# main_schematic.net
KiCad netlist of a schematic drawn in Altium Designer
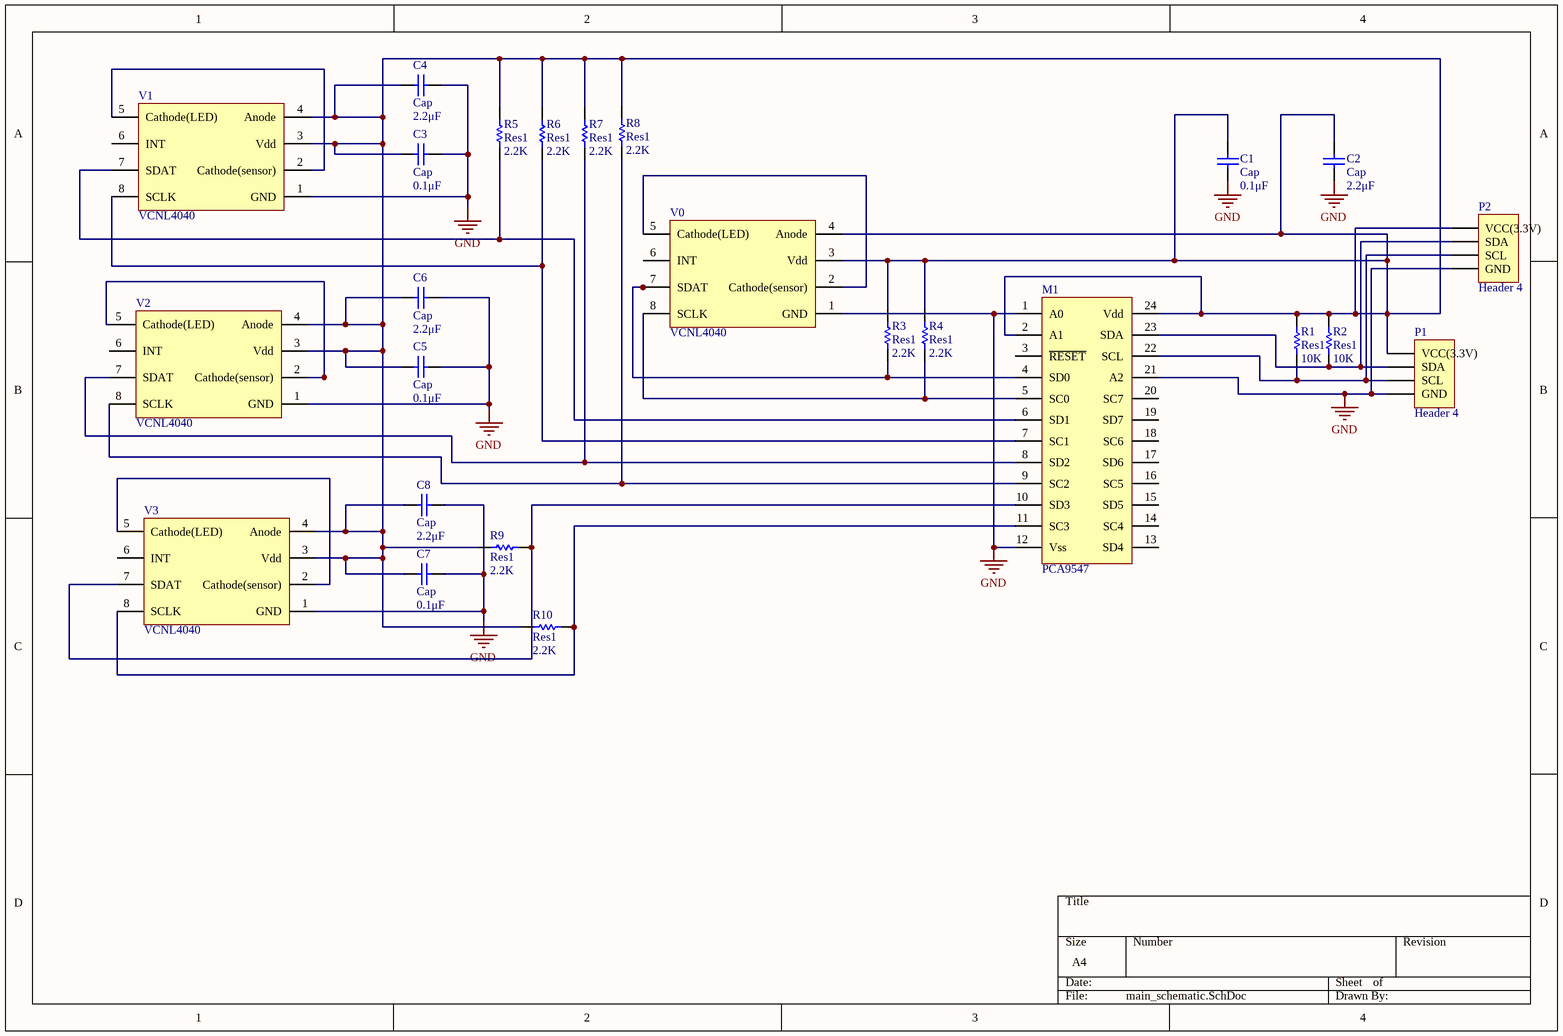
[diagram p0: main_schematic.SchDoc]

(export (version "E")
  (design (tool "Eeschema 10.0.6"))
  (components
    (comp (ref "C1")
      (value "Cap")
      (footprint "1608[0603]")
      (description "Capacitor")
      (fields (field (name "ALTIUM_VALUE") "0.1μF") (field (name "PUBLISHER") "Altium Limited"))
      (libsource (lib "Miscellaneous Devices") (part "Cap"))
    )
    (comp (ref "C2")
      (value "Cap")
      (footprint "1608[0603]")
      (description "Capacitor")
      (fields (field (name "ALTIUM_VALUE") "2.2μF") (field (name "PUBLISHER") "Altium Limited"))
      (libsource (lib "Miscellaneous Devices") (part "Cap"))
    )
    (comp (ref "C3")
      (value "Cap")
      (footprint "1608[0603]")
      (description "Capacitor")
      (fields (field (name "ALTIUM_VALUE") "0.1μF") (field (name "PUBLISHER") "Altium Limited"))
      (libsource (lib "Miscellaneous Devices") (part "Cap"))
    )
    (comp (ref "C4")
      (value "Cap")
      (footprint "1608[0603]")
      (description "Capacitor")
      (fields (field (name "ALTIUM_VALUE") "2.2μF") (field (name "PUBLISHER") "Altium Limited"))
      (libsource (lib "Miscellaneous Devices") (part "Cap"))
    )
    (comp (ref "C5")
      (value "Cap")
      (footprint "1608[0603]")
      (description "Capacitor")
      (fields (field (name "ALTIUM_VALUE") "0.1μF") (field (name "PUBLISHER") "Altium Limited"))
      (libsource (lib "Miscellaneous Devices") (part "Cap"))
    )
    (comp (ref "C6")
      (value "Cap")
      (footprint "1608[0603]")
      (description "Capacitor")
      (fields (field (name "ALTIUM_VALUE") "2.2μF") (field (name "PUBLISHER") "Altium Limited"))
      (libsource (lib "Miscellaneous Devices") (part "Cap"))
    )
    (comp (ref "C7")
      (value "Cap")
      (footprint "1608[0603]")
      (description "Capacitor")
      (fields (field (name "ALTIUM_VALUE") "0.1μF") (field (name "PUBLISHER") "Altium Limited"))
      (libsource (lib "Miscellaneous Devices") (part "Cap"))
    )
    (comp (ref "C8")
      (value "Cap")
      (footprint "1608[0603]")
      (description "Capacitor")
      (fields (field (name "ALTIUM_VALUE") "2.2μF") (field (name "PUBLISHER") "Altium Limited"))
      (libsource (lib "Miscellaneous Devices") (part "Cap"))
    )
    (comp (ref "M1") (value "PCA9547") (footprint "TSSOP24") (libsource (lib "PCA9547") (part "PCA9547")))
    (comp (ref "P1")
      (value "Header 4")
      (footprint "HDR1X4")
      (description "Header, 4-Pin")
      (fields (field (name "PUBLISHER") "Altium Limited"))
      (libsource (lib "Miscellaneous Connectors") (part "Header 4"))
    )
    (comp (ref "P2")
      (value "Header 4")
      (footprint "HDR1X4")
      (description "Header, 4-Pin")
      (fields (field (name "PUBLISHER") "Altium Limited"))
      (libsource (lib "Miscellaneous Connectors") (part "Header 4"))
    )
    (comp (ref "R1")
      (value "Res1")
      (footprint "1608[0603]")
      (description "Resistor")
      (fields (field (name "ALTIUM_VALUE") "10K") (field (name "PUBLISHER") "Altium Limited"))
      (libsource (lib "Miscellaneous Devices") (part "Res1"))
    )
    (comp (ref "R2")
      (value "Res1")
      (footprint "1608[0603]")
      (description "Resistor")
      (fields (field (name "ALTIUM_VALUE") "10K") (field (name "PUBLISHER") "Altium Limited"))
      (libsource (lib "Miscellaneous Devices") (part "Res1"))
    )
    (comp (ref "R3")
      (value "Res1")
      (footprint "1608[0603]")
      (description "Resistor")
      (fields (field (name "ALTIUM_VALUE") "2.2K") (field (name "PUBLISHER") "Altium Limited"))
      (libsource (lib "Miscellaneous Devices") (part "Res1"))
    )
    (comp (ref "R4")
      (value "Res1")
      (footprint "1608[0603]")
      (description "Resistor")
      (fields (field (name "ALTIUM_VALUE") "2.2K") (field (name "PUBLISHER") "Altium Limited"))
      (libsource (lib "Miscellaneous Devices") (part "Res1"))
    )
    (comp (ref "R5")
      (value "Res1")
      (footprint "1608[0603]")
      (description "Resistor")
      (fields (field (name "ALTIUM_VALUE") "2.2K") (field (name "PUBLISHER") "Altium Limited"))
      (libsource (lib "Miscellaneous Devices") (part "Res1"))
    )
    (comp (ref "R6")
      (value "Res1")
      (footprint "1608[0603]")
      (description "Resistor")
      (fields (field (name "ALTIUM_VALUE") "2.2K") (field (name "PUBLISHER") "Altium Limited"))
      (libsource (lib "Miscellaneous Devices") (part "Res1"))
    )
    (comp (ref "R7")
      (value "Res1")
      (footprint "1608[0603]")
      (description "Resistor")
      (fields (field (name "ALTIUM_VALUE") "2.2K") (field (name "PUBLISHER") "Altium Limited"))
      (libsource (lib "Miscellaneous Devices") (part "Res1"))
    )
    (comp (ref "R8")
      (value "Res1")
      (footprint "1608[0603]")
      (description "Resistor")
      (fields (field (name "ALTIUM_VALUE") "2.2K") (field (name "PUBLISHER") "Altium Limited"))
      (libsource (lib "Miscellaneous Devices") (part "Res1"))
    )
    (comp (ref "R9")
      (value "Res1")
      (footprint "1608[0603]")
      (description "Resistor")
      (fields (field (name "ALTIUM_VALUE") "2.2K") (field (name "PUBLISHER") "Altium Limited"))
      (libsource (lib "Miscellaneous Devices") (part "Res1"))
    )
    (comp (ref "R10")
      (value "Res1")
      (footprint "1608[0603]")
      (description "Resistor")
      (fields (field (name "ALTIUM_VALUE") "2.2K") (field (name "PUBLISHER") "Altium Limited"))
      (libsource (lib "Miscellaneous Devices") (part "Res1"))
    )
    (comp (ref "V0") (value "VCNL4040") (footprint "SOP8") (libsource (lib "VCNL4040") (part "Component_1")))
    (comp (ref "V1") (value "VCNL4040") (footprint "SOP8") (libsource (lib "VCNL4040") (part "Component_1")))
    (comp (ref "V2") (value "VCNL4040") (footprint "SOP8") (libsource (lib "VCNL4040") (part "Component_1")))
    (comp (ref "V3") (value "VCNL4040") (footprint "SOP8") (libsource (lib "VCNL4040") (part "Component_1")))
  )
  (nets
    (net (code "1") (name "GND") (class "Default")
      (node (ref "C1") (pin "1") (pinfunction "1_1") (pintype "passive"))
      (node (ref "C2") (pin "1") (pinfunction "1_1") (pintype "passive"))
      (node (ref "C3") (pin "1") (pinfunction "1_1") (pintype "passive"))
      (node (ref "C4") (pin "1") (pinfunction "1_1") (pintype "passive"))
      (node (ref "C5") (pin "1") (pinfunction "1_1") (pintype "passive"))
      (node (ref "C6") (pin "1") (pinfunction "1_1") (pintype "passive"))
      (node (ref "C7") (pin "1") (pinfunction "1_1") (pintype "passive"))
      (node (ref "C8") (pin "1") (pinfunction "1_1") (pintype "passive"))
      (node (ref "M1") (pin "1") (pinfunction "A0_1") (pintype "passive"))
      (node (ref "M1") (pin "12") (pinfunction "Vss_12") (pintype "passive"))
      (node (ref "M1") (pin "21") (pinfunction "A2_21") (pintype "passive"))
      (node (ref "P1") (pin "4") (pinfunction "GND_4") (pintype "passive"))
      (node (ref "P2") (pin "4") (pinfunction "GND_4") (pintype "passive"))
      (node (ref "V0") (pin "1") (pinfunction "GND_1") (pintype "passive"))
      (node (ref "V1") (pin "1") (pinfunction "GND_1") (pintype "passive"))
      (node (ref "V2") (pin "1") (pinfunction "GND_1") (pintype "passive"))
      (node (ref "V3") (pin "1") (pinfunction "GND_1") (pintype "passive"))
    )
    (net (code "2") (name "Net-(M1-A1)") (class "Default")
      (node (ref "C1") (pin "2") (pinfunction "2_2") (pintype "passive"))
      (node (ref "C2") (pin "2") (pinfunction "2_2") (pintype "passive"))
      (node (ref "C3") (pin "2") (pinfunction "2_2") (pintype "passive"))
      (node (ref "C4") (pin "2") (pinfunction "2_2") (pintype "passive"))
      (node (ref "C5") (pin "2") (pinfunction "2_2") (pintype "passive"))
      (node (ref "C6") (pin "2") (pinfunction "2_2") (pintype "passive"))
      (node (ref "C7") (pin "2") (pinfunction "2_2") (pintype "passive"))
      (node (ref "C8") (pin "2") (pinfunction "2_2") (pintype "passive"))
      (node (ref "M1") (pin "2") (pinfunction "A1_2") (pintype "passive"))
      (node (ref "M1") (pin "24") (pinfunction "Vdd_24") (pintype "passive"))
      (node (ref "P1") (pin "1") (pinfunction "VCC(3.3V)_1") (pintype "passive"))
      (node (ref "P2") (pin "1") (pinfunction "VCC(3.3V)_1") (pintype "passive"))
      (node (ref "R1") (pin "2") (pinfunction "2_2") (pintype "passive"))
      (node (ref "R10") (pin "2") (pinfunction "2_2") (pintype "passive"))
      (node (ref "R2") (pin "2") (pinfunction "2_2") (pintype "passive"))
      (node (ref "R3") (pin "2") (pinfunction "2_2") (pintype "passive"))
      (node (ref "R4") (pin "2") (pinfunction "2_2") (pintype "passive"))
      (node (ref "R5") (pin "2") (pinfunction "2_2") (pintype "passive"))
      (node (ref "R6") (pin "2") (pinfunction "2_2") (pintype "passive"))
      (node (ref "R7") (pin "2") (pinfunction "2_2") (pintype "passive"))
      (node (ref "R8") (pin "2") (pinfunction "2_2") (pintype "passive"))
      (node (ref "R9") (pin "2") (pinfunction "2_2") (pintype "passive"))
      (node (ref "V0") (pin "3") (pinfunction "Vdd_3") (pintype "passive"))
      (node (ref "V0") (pin "4") (pinfunction "Anode_4") (pintype "passive"))
      (node (ref "V1") (pin "3") (pinfunction "Vdd_3") (pintype "passive"))
      (node (ref "V1") (pin "4") (pinfunction "Anode_4") (pintype "passive"))
      (node (ref "V2") (pin "3") (pinfunction "Vdd_3") (pintype "passive"))
      (node (ref "V2") (pin "4") (pinfunction "Anode_4") (pintype "passive"))
      (node (ref "V3") (pin "3") (pinfunction "Vdd_3") (pintype "passive"))
      (node (ref "V3") (pin "4") (pinfunction "Anode_4") (pintype "passive"))
    )
    (net (code "3") (name "Net-(M1-SC0)") (class "Default")
      (node (ref "M1") (pin "5") (pinfunction "SC0_5") (pintype "passive"))
      (node (ref "R4") (pin "1") (pinfunction "1_1") (pintype "passive"))
      (node (ref "V0") (pin "8") (pinfunction "SCLK_8") (pintype "passive"))
    )
    (net (code "4") (name "Net-(M1-SC1)") (class "Default")
      (node (ref "M1") (pin "7") (pinfunction "SC1_7") (pintype "passive"))
      (node (ref "R6") (pin "1") (pinfunction "1_1") (pintype "passive"))
      (node (ref "V1") (pin "8") (pinfunction "SCLK_8") (pintype "passive"))
    )
    (net (code "5") (name "Net-(M1-SC2)") (class "Default")
      (node (ref "M1") (pin "9") (pinfunction "SC2_9") (pintype "passive"))
      (node (ref "R8") (pin "1") (pinfunction "1_1") (pintype "passive"))
      (node (ref "V2") (pin "8") (pinfunction "SCLK_8") (pintype "passive"))
    )
    (net (code "6") (name "Net-(M1-SC3)") (class "Default")
      (node (ref "M1") (pin "11") (pinfunction "SC3_11") (pintype "passive"))
      (node (ref "R10") (pin "1") (pinfunction "1_1") (pintype "passive"))
      (node (ref "V3") (pin "8") (pinfunction "SCLK_8") (pintype "passive"))
    )
    (net (code "7") (name "Net-(M1-SCL)") (class "Default")
      (node (ref "M1") (pin "22") (pinfunction "SCL_22") (pintype "passive"))
      (node (ref "P1") (pin "3") (pinfunction "SCL_3") (pintype "passive"))
      (node (ref "P2") (pin "3") (pinfunction "SCL_3") (pintype "passive"))
      (node (ref "R1") (pin "1") (pinfunction "1_1") (pintype "passive"))
    )
    (net (code "8") (name "Net-(M1-SD0)") (class "Default")
      (node (ref "M1") (pin "4") (pinfunction "SD0_4") (pintype "passive"))
      (node (ref "R3") (pin "1") (pinfunction "1_1") (pintype "passive"))
      (node (ref "V0") (pin "7") (pinfunction "SDAT_7") (pintype "passive"))
    )
    (net (code "9") (name "Net-(M1-SD1)") (class "Default")
      (node (ref "M1") (pin "6") (pinfunction "SD1_6") (pintype "passive"))
      (node (ref "R5") (pin "1") (pinfunction "1_1") (pintype "passive"))
      (node (ref "V1") (pin "7") (pinfunction "SDAT_7") (pintype "passive"))
    )
    (net (code "10") (name "Net-(M1-SD2)") (class "Default")
      (node (ref "M1") (pin "8") (pinfunction "SD2_8") (pintype "passive"))
      (node (ref "R7") (pin "1") (pinfunction "1_1") (pintype "passive"))
      (node (ref "V2") (pin "7") (pinfunction "SDAT_7") (pintype "passive"))
    )
    (net (code "11") (name "Net-(M1-SD3)") (class "Default")
      (node (ref "M1") (pin "10") (pinfunction "SD3_10") (pintype "passive"))
      (node (ref "R9") (pin "1") (pinfunction "1_1") (pintype "passive"))
      (node (ref "V3") (pin "7") (pinfunction "SDAT_7") (pintype "passive"))
    )
    (net (code "12") (name "Net-(M1-SDA)") (class "Default")
      (node (ref "M1") (pin "23") (pinfunction "SDA_23") (pintype "passive"))
      (node (ref "P1") (pin "2") (pinfunction "SDA_2") (pintype "passive"))
      (node (ref "P2") (pin "2") (pinfunction "SDA_2") (pintype "passive"))
      (node (ref "R2") (pin "1") (pinfunction "1_1") (pintype "passive"))
    )
    (net (code "13") (name "Net-(V0-Cathode(LED))") (class "Default")
      (node (ref "V0") (pin "2") (pinfunction "Cathode(sensor)_2") (pintype "passive"))
      (node (ref "V0") (pin "5") (pinfunction "Cathode(LED)_5") (pintype "passive"))
    )
    (net (code "14") (name "Net-(V1-Cathode(LED))") (class "Default")
      (node (ref "V1") (pin "2") (pinfunction "Cathode(sensor)_2") (pintype "passive"))
      (node (ref "V1") (pin "5") (pinfunction "Cathode(LED)_5") (pintype "passive"))
    )
    (net (code "15") (name "Net-(V2-Cathode(LED))") (class "Default")
      (node (ref "V2") (pin "2") (pinfunction "Cathode(sensor)_2") (pintype "passive"))
      (node (ref "V2") (pin "5") (pinfunction "Cathode(LED)_5") (pintype "passive"))
    )
    (net (code "16") (name "Net-(V3-Cathode(LED))") (class "Default")
      (node (ref "V3") (pin "2") (pinfunction "Cathode(sensor)_2") (pintype "passive"))
      (node (ref "V3") (pin "5") (pinfunction "Cathode(LED)_5") (pintype "passive"))
    )
    (net (code "17") (name "unconnected-(M1-SC4-Pad14)") (class "Default")
      (node (ref "M1") (pin "14") (pinfunction "SC4_14") (pintype "passive"))
    )
    (net (code "18") (name "unconnected-(M1-SC5-Pad16)") (class "Default")
      (node (ref "M1") (pin "16") (pinfunction "SC5_16") (pintype "passive"))
    )
    (net (code "19") (name "unconnected-(M1-SC6-Pad18)") (class "Default")
      (node (ref "M1") (pin "18") (pinfunction "SC6_18") (pintype "passive"))
    )
    (net (code "20") (name "unconnected-(M1-SC7-Pad20)") (class "Default")
      (node (ref "M1") (pin "20") (pinfunction "SC7_20") (pintype "passive"))
    )
    (net (code "21") (name "unconnected-(M1-SD4-Pad13)") (class "Default")
      (node (ref "M1") (pin "13") (pinfunction "SD4_13") (pintype "passive"))
    )
    (net (code "22") (name "unconnected-(M1-SD5-Pad15)") (class "Default")
      (node (ref "M1") (pin "15") (pinfunction "SD5_15") (pintype "passive"))
    )
    (net (code "23") (name "unconnected-(M1-SD6-Pad17)") (class "Default")
      (node (ref "M1") (pin "17") (pinfunction "SD6_17") (pintype "passive"))
    )
    (net (code "24") (name "unconnected-(M1-SD7-Pad19)") (class "Default")
      (node (ref "M1") (pin "19") (pinfunction "SD7_19") (pintype "passive"))
    )
    (net (code "25") (name "unconnected-(M1-~{RESET}-Pad3)") (class "Default")
      (node (ref "M1") (pin "3") (pinfunction "~{RESET}_3") (pintype "passive"))
    )
    (net (code "26") (name "unconnected-(V0-INT-Pad6)") (class "Default")
      (node (ref "V0") (pin "6") (pinfunction "INT_6") (pintype "passive"))
    )
    (net (code "27") (name "unconnected-(V1-INT-Pad6)") (class "Default")
      (node (ref "V1") (pin "6") (pinfunction "INT_6") (pintype "passive"))
    )
    (net (code "28") (name "unconnected-(V2-INT-Pad6)") (class "Default")
      (node (ref "V2") (pin "6") (pinfunction "INT_6") (pintype "passive"))
    )
    (net (code "29") (name "unconnected-(V3-INT-Pad6)") (class "Default")
      (node (ref "V3") (pin "6") (pinfunction "INT_6") (pintype "passive"))
    )
  )
)
